# Displays.net
KiCad netlist of a schematic drawn in Altium Designer
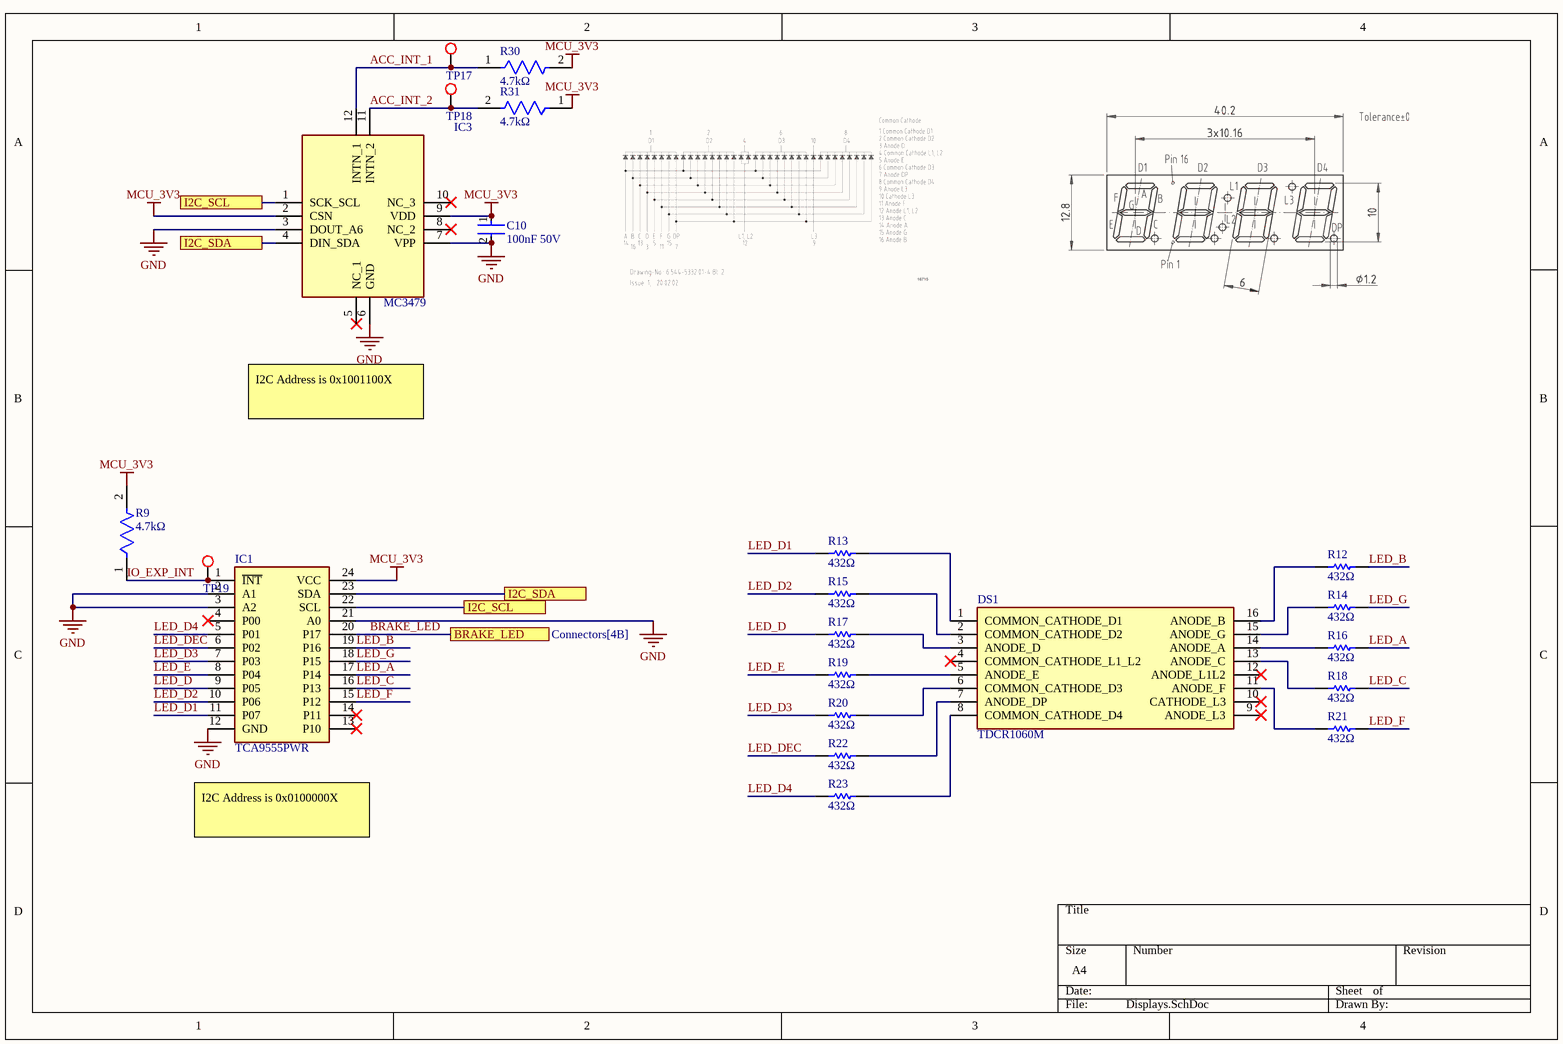
[diagram p0: Displays.SchDoc]

(export (version "E")
  (design (tool "Eeschema 10.0.6"))
  (components
    (comp (ref "C10")
      (value "100nF 50V")
      (footprint "FP-CL31-IPC_C")
      (description "Cap Ceramic 100nF 50V X7R ±10% SMD 1206 +125°C Embossed T/R")
      (fields (field (name "TOLERANCE") "10%"))
      (libsource (lib "Altium Content Vault") (part "b4654b650e69147ec39a6b967a45e02"))
    )
    (comp (ref "DS1")
      (value "TDCR1060M")
      (footprint "SamacSys:DIPS1016W50P254L4020H725Q16N")
      (description "Display")
      (fields (field (name "MOUSER PART NUMBER") "78-TDCR1060M"))
      (libsource (lib "*") (part "TDCR1060M"))
    )
    (comp (ref "IC1")
      (value "TCA9555PWR")
      (footprint "SamacSys:SOP65P640X120-24N")
      (description "Integrated Circuit")
      (fields (field (name "MOUSER PART NUMBER") "595-TCA9555PWR"))
      (libsource (lib "*") (part "TCA9555PWR"))
    )
    (comp (ref "IC3")
      (value "MC3479")
      (footprint "MC3479")
      (description "Accelerometers Small Digital 3-axis Accelerometer Sensor")
      (fields (field (name "MOUSER PART NUMBER") "498-MC3479"))
      (libsource (lib "Schlib1") (part "MC3479"))
    )
    (comp (ref "R9")
      (value "4.7kΩ")
      (footprint "FP-RT0805-MFG")
      (description "RES SMD 4.7K OHM 1% 1/8W 0805")
      (fields (field (name "TOLERANCE") "0.0001") (field (name "MANUFACTURER PART NUMBER") "RT0805FRE074K7L"))
      (libsource (lib "Altium Content Vault") (part "1029c3af85768c4190bb7ad29bc67b5"))
    )
    (comp (ref "R12")
      (value "432Ω")
      (footprint "RESC2013X50X30NL20T20")
      (fields (field (name "PART NUMBER") "CRCW0805432RFKEA") (field (name "MANUFACTURER") "Vishay Dale"))
      (libsource (lib "Altium Content Vault") (part "RES"))
    )
    (comp (ref "R13")
      (value "432Ω")
      (footprint "RESC2013X50X30NL20T20")
      (fields (field (name "PART NUMBER") "CRCW0805432RFKEA") (field (name "MANUFACTURER") "Vishay Dale"))
      (libsource (lib "Altium Content Vault") (part "RES"))
    )
    (comp (ref "R14")
      (value "432Ω")
      (footprint "RESC2013X50X30NL20T20")
      (fields (field (name "PART NUMBER") "CRCW0805432RFKEA") (field (name "MANUFACTURER") "Vishay Dale"))
      (libsource (lib "Altium Content Vault") (part "RES"))
    )
    (comp (ref "R15")
      (value "432Ω")
      (footprint "RESC2013X50X30NL20T20")
      (fields (field (name "PART NUMBER") "CRCW0805432RFKEA") (field (name "MANUFACTURER") "Vishay Dale"))
      (libsource (lib "Altium Content Vault") (part "RES"))
    )
    (comp (ref "R16")
      (value "432Ω")
      (footprint "RESC2013X50X30NL20T20")
      (fields (field (name "PART NUMBER") "CRCW0805432RFKEA") (field (name "MANUFACTURER") "Vishay Dale"))
      (libsource (lib "Altium Content Vault") (part "RES"))
    )
    (comp (ref "R17")
      (value "432Ω")
      (footprint "RESC2013X50X30NL20T20")
      (fields (field (name "PART NUMBER") "CRCW0805432RFKEA") (field (name "MANUFACTURER") "Vishay Dale"))
      (libsource (lib "Altium Content Vault") (part "RES"))
    )
    (comp (ref "R18")
      (value "432Ω")
      (footprint "RESC2013X50X30NL20T20")
      (fields (field (name "PART NUMBER") "CRCW0805432RFKEA") (field (name "MANUFACTURER") "Vishay Dale"))
      (libsource (lib "Altium Content Vault") (part "RES"))
    )
    (comp (ref "R19")
      (value "432Ω")
      (footprint "RESC2013X50X30NL20T20")
      (fields (field (name "PART NUMBER") "CRCW0805432RFKEA") (field (name "MANUFACTURER") "Vishay Dale"))
      (libsource (lib "Altium Content Vault") (part "RES"))
    )
    (comp (ref "R20")
      (value "432Ω")
      (footprint "RESC2013X50X30NL20T20")
      (fields (field (name "PART NUMBER") "CRCW0805432RFKEA") (field (name "MANUFACTURER") "Vishay Dale"))
      (libsource (lib "Altium Content Vault") (part "RES"))
    )
    (comp (ref "R21")
      (value "432Ω")
      (footprint "RESC2013X50X30NL20T20")
      (fields (field (name "PART NUMBER") "CRCW0805432RFKEA") (field (name "MANUFACTURER") "Vishay Dale"))
      (libsource (lib "Altium Content Vault") (part "RES"))
    )
    (comp (ref "R22")
      (value "432Ω")
      (footprint "RESC2013X50X30NL20T20")
      (fields (field (name "PART NUMBER") "CRCW0805432RFKEA") (field (name "MANUFACTURER") "Vishay Dale"))
      (libsource (lib "Altium Content Vault") (part "RES"))
    )
    (comp (ref "R23")
      (value "432Ω")
      (footprint "RESC2013X50X30NL20T20")
      (fields (field (name "PART NUMBER") "CRCW0805432RFKEA") (field (name "MANUFACTURER") "Vishay Dale"))
      (libsource (lib "Altium Content Vault") (part "RES"))
    )
    (comp (ref "R30")
      (value "4.7kΩ")
      (footprint "FP-RT0805-MFG")
      (description "RES SMD 4.7K OHM 1% 1/8W 0805")
      (fields (field (name "TOLERANCE") "0.0001") (field (name "MANUFACTURER PART NUMBER") "RT0805FRE074K7L"))
      (libsource (lib "Altium Content Vault") (part "1029c3af85768c4190bb7ad29bc67b5"))
    )
    (comp (ref "R31")
      (value "4.7kΩ")
      (footprint "FP-RT0805-MFG")
      (description "RES SMD 4.7K OHM 1% 1/8W 0805")
      (fields (field (name "TOLERANCE") "0.0001") (field (name "MANUFACTURER PART NUMBER") "RT0805FRE074K7L"))
      (libsource (lib "Altium Content Vault") (part "1029c3af85768c4190bb7ad29bc67b5"))
    )
    (comp (ref "TP17") (value "TP") (footprint "Testpoint") (libsource (lib "Schlib1") (part "Testpoint")))
    (comp (ref "TP18") (value "TP") (footprint "Testpoint") (libsource (lib "Schlib1") (part "Testpoint")))
    (comp (ref "TP19") (value "TP") (footprint "Testpoint") (libsource (lib "Schlib1") (part "Testpoint")))
  )
  (nets
    (net (code "1") (name "/ACC_INT_1") (class "Default")
      (node (ref "IC3") (pin "12") (pinfunction "INTN_1_12") (pintype "passive"))
      (node (ref "R30") (pin "1") (pinfunction "1_1") (pintype "passive"))
      (node (ref "TP17") (pin "0") (pinfunction "0_0") (pintype "passive"))
    )
    (net (code "2") (name "/ACC_INT_2") (class "Default")
      (node (ref "IC3") (pin "11") (pinfunction "INTN_2_11") (pintype "passive"))
      (node (ref "R31") (pin "2") (pinfunction "2_2") (pintype "passive"))
      (node (ref "TP18") (pin "0") (pinfunction "0_0") (pintype "passive"))
    )
    (net (code "3") (name "/BRAKE_LED") (class "Default")
      (node (ref "IC1") (pin "20") (pinfunction "P17_20") (pintype "passive"))
    )
    (net (code "4") (name "/I2C_SCL") (class "Default")
      (node (ref "IC1") (pin "22") (pinfunction "SCL_22") (pintype "passive"))
      (node (ref "IC3") (pin "1") (pinfunction "SCK_SCL_1") (pintype "passive"))
    )
    (net (code "5") (name "/I2C_SDA") (class "Default")
      (node (ref "IC1") (pin "23") (pinfunction "SDA_23") (pintype "passive"))
      (node (ref "IC3") (pin "4") (pinfunction "DIN_SDA_4") (pintype "passive"))
    )
    (net (code "6") (name "/IO_EXP_INT") (class "Default")
      (node (ref "IC1") (pin "1") (pinfunction "~{INT}_1") (pintype "passive"))
      (node (ref "R9") (pin "1") (pinfunction "1_1") (pintype "passive"))
      (node (ref "TP19") (pin "0") (pinfunction "0_0") (pintype "passive"))
    )
    (net (code "7") (name "/LED_A") (class "Default")
      (node (ref "IC1") (pin "17") (pinfunction "P14_17") (pintype "passive"))
      (node (ref "R16") (pin "2") (pinfunction "2_2") (pintype "passive"))
    )
    (net (code "8") (name "/LED_B") (class "Default")
      (node (ref "IC1") (pin "19") (pinfunction "P16_19") (pintype "passive"))
      (node (ref "R12") (pin "2") (pinfunction "2_2") (pintype "passive"))
    )
    (net (code "9") (name "/LED_C") (class "Default")
      (node (ref "IC1") (pin "16") (pinfunction "P13_16") (pintype "passive"))
      (node (ref "R18") (pin "2") (pinfunction "2_2") (pintype "passive"))
    )
    (net (code "10") (name "/LED_D") (class "Default")
      (node (ref "IC1") (pin "9") (pinfunction "P05_9") (pintype "passive"))
      (node (ref "R17") (pin "1") (pinfunction "1_1") (pintype "passive"))
    )
    (net (code "11") (name "/LED_D1") (class "Default")
      (node (ref "IC1") (pin "11") (pinfunction "P07_11") (pintype "passive"))
      (node (ref "R13") (pin "1") (pinfunction "1_1") (pintype "passive"))
    )
    (net (code "12") (name "/LED_D2") (class "Default")
      (node (ref "IC1") (pin "10") (pinfunction "P06_10") (pintype "passive"))
      (node (ref "R15") (pin "1") (pinfunction "1_1") (pintype "passive"))
    )
    (net (code "13") (name "/LED_D3") (class "Default")
      (node (ref "IC1") (pin "7") (pinfunction "P03_7") (pintype "passive"))
      (node (ref "R20") (pin "1") (pinfunction "1_1") (pintype "passive"))
    )
    (net (code "14") (name "/LED_D4") (class "Default")
      (node (ref "IC1") (pin "5") (pinfunction "P01_5") (pintype "passive"))
      (node (ref "R23") (pin "1") (pinfunction "1_1") (pintype "passive"))
    )
    (net (code "15") (name "/LED_DEC") (class "Default")
      (node (ref "IC1") (pin "6") (pinfunction "P02_6") (pintype "passive"))
      (node (ref "R22") (pin "1") (pinfunction "1_1") (pintype "passive"))
    )
    (net (code "16") (name "/LED_E") (class "Default")
      (node (ref "IC1") (pin "8") (pinfunction "P04_8") (pintype "passive"))
      (node (ref "R19") (pin "1") (pinfunction "1_1") (pintype "passive"))
    )
    (net (code "17") (name "/LED_F") (class "Default")
      (node (ref "IC1") (pin "15") (pinfunction "P12_15") (pintype "passive"))
      (node (ref "R21") (pin "2") (pinfunction "2_2") (pintype "passive"))
    )
    (net (code "18") (name "/LED_G") (class "Default")
      (node (ref "IC1") (pin "18") (pinfunction "P15_18") (pintype "passive"))
      (node (ref "R14") (pin "2") (pinfunction "2_2") (pintype "passive"))
    )
    (net (code "19") (name "GND") (class "Default")
      (node (ref "C10") (pin "2") (pinfunction "2_2") (pintype "passive"))
      (node (ref "IC1") (pin "12") (pinfunction "GND_12") (pintype "passive"))
      (node (ref "IC1") (pin "2") (pinfunction "A1_2") (pintype "passive"))
      (node (ref "IC1") (pin "21") (pinfunction "A0_21") (pintype "passive"))
      (node (ref "IC1") (pin "3") (pinfunction "A2_3") (pintype "passive"))
      (node (ref "IC3") (pin "3") (pinfunction "DOUT_A6_3") (pintype "passive"))
      (node (ref "IC3") (pin "6") (pinfunction "GND_6") (pintype "passive"))
      (node (ref "IC3") (pin "7") (pinfunction "VPP_7") (pintype "passive"))
    )
    (net (code "20") (name "MCU_3V3") (class "Default")
      (node (ref "C10") (pin "1") (pinfunction "1_1") (pintype "passive"))
      (node (ref "IC1") (pin "24") (pinfunction "VCC_24") (pintype "passive"))
      (node (ref "IC3") (pin "2") (pinfunction "CSN_2") (pintype "passive"))
      (node (ref "IC3") (pin "9") (pinfunction "VDD_9") (pintype "passive"))
      (node (ref "R30") (pin "2") (pinfunction "2_2") (pintype "passive"))
      (node (ref "R31") (pin "1") (pinfunction "1_1") (pintype "passive"))
      (node (ref "R9") (pin "2") (pinfunction "2_2") (pintype "passive"))
    )
    (net (code "21") (name "Net-(DS1-ANODE_A)") (class "Default")
      (node (ref "DS1") (pin "14") (pinfunction "ANODE_A_14") (pintype "passive"))
      (node (ref "R16") (pin "1") (pinfunction "1_1") (pintype "passive"))
    )
    (net (code "22") (name "Net-(DS1-ANODE_B)") (class "Default")
      (node (ref "DS1") (pin "16") (pinfunction "ANODE_B_16") (pintype "passive"))
      (node (ref "R12") (pin "1") (pinfunction "1_1") (pintype "passive"))
    )
    (net (code "23") (name "Net-(DS1-ANODE_C)") (class "Default")
      (node (ref "DS1") (pin "13") (pinfunction "ANODE_C_13") (pintype "passive"))
      (node (ref "R18") (pin "1") (pinfunction "1_1") (pintype "passive"))
    )
    (net (code "24") (name "Net-(DS1-ANODE_D)") (class "Default")
      (node (ref "DS1") (pin "3") (pinfunction "ANODE_D_3") (pintype "passive"))
      (node (ref "R17") (pin "2") (pinfunction "2_2") (pintype "passive"))
    )
    (net (code "25") (name "Net-(DS1-ANODE_DP)") (class "Default")
      (node (ref "DS1") (pin "7") (pinfunction "ANODE_DP_7") (pintype "passive"))
      (node (ref "R22") (pin "2") (pinfunction "2_2") (pintype "passive"))
    )
    (net (code "26") (name "Net-(DS1-ANODE_E)") (class "Default")
      (node (ref "DS1") (pin "5") (pinfunction "ANODE_E_5") (pintype "passive"))
      (node (ref "R19") (pin "2") (pinfunction "2_2") (pintype "passive"))
    )
    (net (code "27") (name "Net-(DS1-ANODE_F)") (class "Default")
      (node (ref "DS1") (pin "11") (pinfunction "ANODE_F_11") (pintype "passive"))
      (node (ref "R21") (pin "1") (pinfunction "1_1") (pintype "passive"))
    )
    (net (code "28") (name "Net-(DS1-ANODE_G)") (class "Default")
      (node (ref "DS1") (pin "15") (pinfunction "ANODE_G_15") (pintype "passive"))
      (node (ref "R14") (pin "1") (pinfunction "1_1") (pintype "passive"))
    )
    (net (code "29") (name "Net-(DS1-COMMON_CATHODE_D1)") (class "Default")
      (node (ref "DS1") (pin "1") (pinfunction "COMMON_CATHODE_D1_1") (pintype "passive"))
      (node (ref "R13") (pin "2") (pinfunction "2_2") (pintype "passive"))
    )
    (net (code "30") (name "Net-(DS1-COMMON_CATHODE_D2)") (class "Default")
      (node (ref "DS1") (pin "2") (pinfunction "COMMON_CATHODE_D2_2") (pintype "passive"))
      (node (ref "R15") (pin "2") (pinfunction "2_2") (pintype "passive"))
    )
    (net (code "31") (name "Net-(DS1-COMMON_CATHODE_D3)") (class "Default")
      (node (ref "DS1") (pin "6") (pinfunction "COMMON_CATHODE_D3_6") (pintype "passive"))
      (node (ref "R20") (pin "2") (pinfunction "2_2") (pintype "passive"))
    )
    (net (code "32") (name "Net-(DS1-COMMON_CATHODE_D4)") (class "Default")
      (node (ref "DS1") (pin "8") (pinfunction "COMMON_CATHODE_D4_8") (pintype "passive"))
      (node (ref "R23") (pin "2") (pinfunction "2_2") (pintype "passive"))
    )
    (net (code "33") (name "unconnected-(DS1-ANODE_L1L2-Pad12)") (class "Default")
      (node (ref "DS1") (pin "12") (pinfunction "ANODE_L1L2_12") (pintype "passive+no_connect"))
    )
    (net (code "34") (name "unconnected-(DS1-ANODE_L3-Pad9)") (class "Default")
      (node (ref "DS1") (pin "9") (pinfunction "ANODE_L3_9") (pintype "passive+no_connect"))
    )
    (net (code "35") (name "unconnected-(DS1-CATHODE_L3-Pad10)") (class "Default")
      (node (ref "DS1") (pin "10") (pinfunction "CATHODE_L3_10") (pintype "passive+no_connect"))
    )
    (net (code "36") (name "unconnected-(DS1-COMMON_CATHODE_L1_L2-Pad4)") (class "Default")
      (node (ref "DS1") (pin "4") (pinfunction "COMMON_CATHODE_L1_L2_4") (pintype "passive+no_connect"))
    )
    (net (code "37") (name "unconnected-(IC1-P00-Pad4)") (class "Default")
      (node (ref "IC1") (pin "4") (pinfunction "P00_4") (pintype "passive+no_connect"))
    )
    (net (code "38") (name "unconnected-(IC1-P10-Pad13)") (class "Default")
      (node (ref "IC1") (pin "13") (pinfunction "P10_13") (pintype "passive+no_connect"))
    )
    (net (code "39") (name "unconnected-(IC1-P11-Pad14)") (class "Default")
      (node (ref "IC1") (pin "14") (pinfunction "P11_14") (pintype "passive+no_connect"))
    )
    (net (code "40") (name "unconnected-(IC3-NC_1-Pad5)") (class "Default")
      (node (ref "IC3") (pin "5") (pinfunction "NC_1_5") (pintype "passive+no_connect"))
    )
    (net (code "41") (name "unconnected-(IC3-NC_2-Pad8)") (class "Default")
      (node (ref "IC3") (pin "8") (pinfunction "NC_2_8") (pintype "passive+no_connect"))
    )
    (net (code "42") (name "unconnected-(IC3-NC_3-Pad10)") (class "Default")
      (node (ref "IC3") (pin "10") (pinfunction "NC_3_10") (pintype "passive+no_connect"))
    )
  )
)
